# PCB_Schematic.net
KiCad netlist of a schematic drawn in Altium Designer
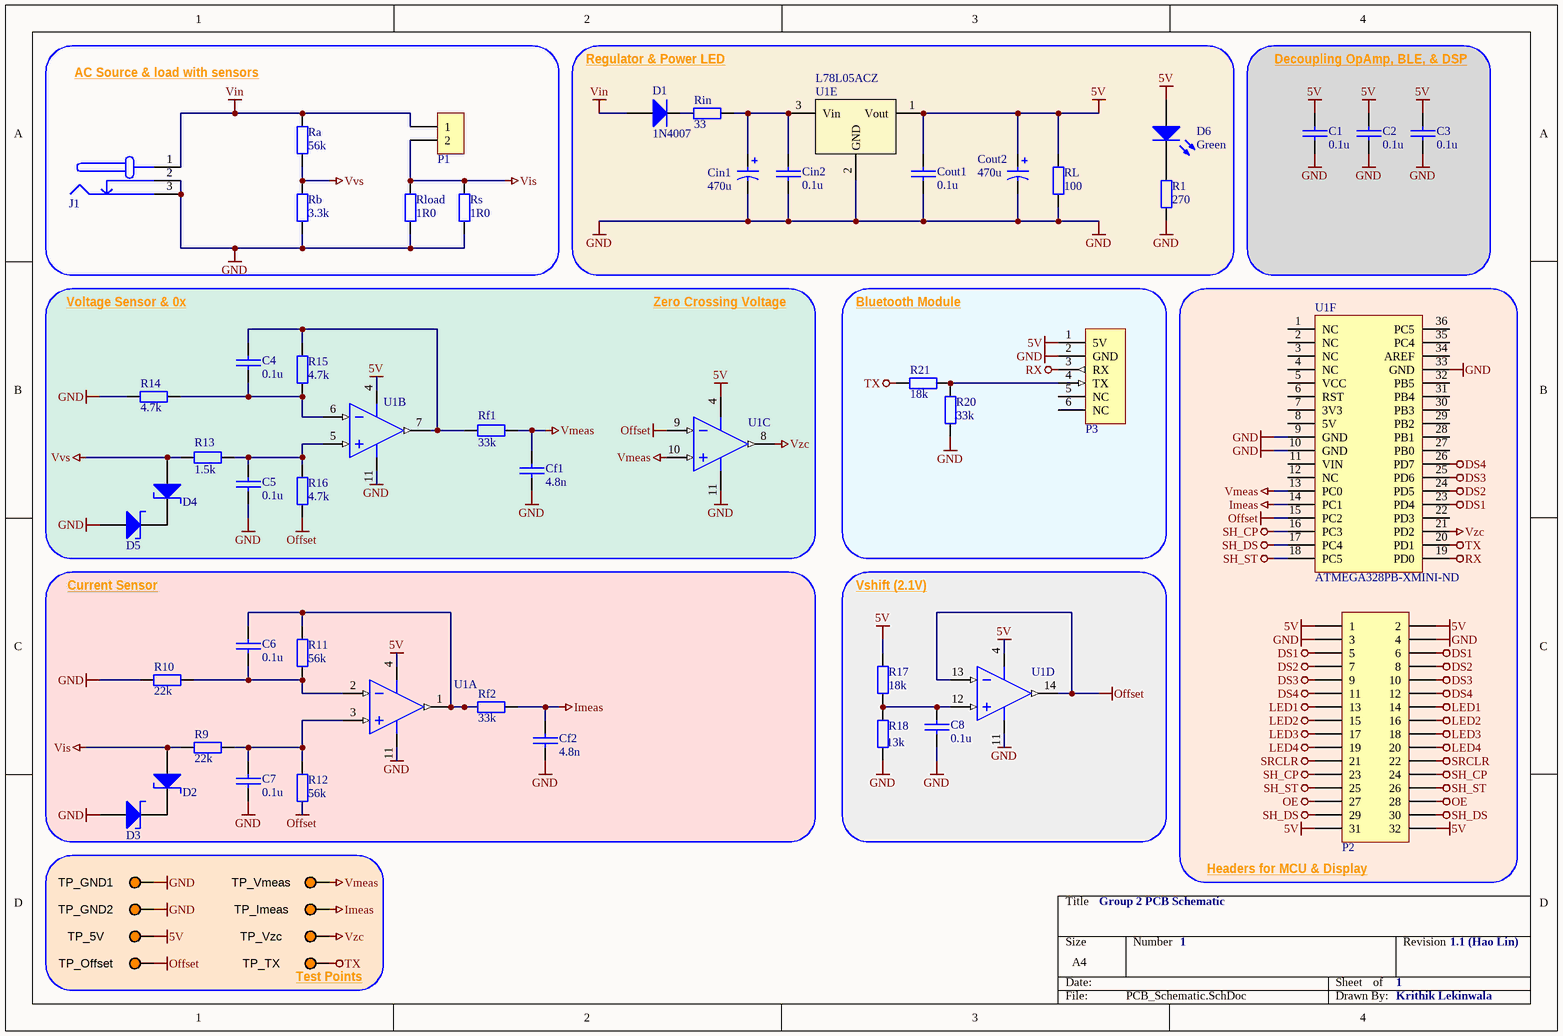
[diagram p0: PCB_Schematic.SchDoc]

(export (version "E")
  (design (tool "Eeschema 10.0.6"))
  (components
    (comp (ref "C1")
      (value "0.1u")
      (footprint "CCAP-5P0")
      (description "SMT ceramic capacitor 0805 size")
      (libsource (lib "EE209_Library") (part "CerCap_TH_5P0"))
    )
    (comp (ref "C2")
      (value "0.1u")
      (footprint "CCAP-5P0")
      (description "SMT ceramic capacitor 0805 size")
      (libsource (lib "EE209_Library") (part "CerCap_TH_5P0"))
    )
    (comp (ref "C3")
      (value "0.1u")
      (footprint "CCAP-5P0")
      (description "SMT ceramic capacitor 0805 size")
      (libsource (lib "EE209_Library") (part "CerCap_TH_5P0"))
    )
    (comp (ref "C4")
      (value "0.1u")
      (footprint "CCAP-5P0")
      (description "SMT ceramic capacitor 0805 size")
      (libsource (lib "EE209_Library") (part "CerCap_TH_5P0"))
    )
    (comp (ref "C5")
      (value "0.1u")
      (footprint "CCAP-5P0")
      (description "SMT ceramic capacitor 0805 size")
      (libsource (lib "EE209_Library") (part "CerCap_TH_5P0"))
    )
    (comp (ref "C6")
      (value "0.1u")
      (footprint "CCAP-5P0")
      (description "SMT ceramic capacitor 0805 size")
      (libsource (lib "EE209_Library") (part "CerCap_TH_5P0"))
    )
    (comp (ref "C7")
      (value "0.1u")
      (footprint "CCAP-5P0")
      (description "SMT ceramic capacitor 0805 size")
      (libsource (lib "EE209_Library") (part "CerCap_TH_5P0"))
    )
    (comp (ref "C8")
      (value "0.1u")
      (footprint "CCAP-5P0")
      (description "SMT ceramic capacitor 0805 size")
      (libsource (lib "EE209_Library") (part "CerCap_TH_5P0"))
    )
    (comp (ref "Cf1")
      (value "4.8n")
      (footprint "CCAP-5P0")
      (description "SMT ceramic capacitor 0805 size")
      (libsource (lib "EE209_Library") (part "CerCap_TH_5P0"))
    )
    (comp (ref "Cf2")
      (value "4.8n")
      (footprint "CCAP-5P0")
      (description "SMT ceramic capacitor 0805 size")
      (libsource (lib "EE209_Library") (part "CerCap_TH_5P0"))
    )
    (comp (ref "Cin1")
      (value "470u")
      (footprint "CAP-RAD-2.5mm Pitch")
      (description "Electrolytic capacitor with radial package, 2mm pitch and 5.2mm diameter")
      (fields (field (name "PUBLISHER") "Altium Limited"))
      (libsource (lib "EE209_Library") (part "ElecCap_TH_2P0"))
    )
    (comp (ref "Cin2")
      (value "0.1u")
      (footprint "CCAP-5P0")
      (description "SMT ceramic capacitor 0805 size")
      (libsource (lib "EE209_Library") (part "CerCap_TH_5P0"))
    )
    (comp (ref "Cout1")
      (value "0.1u")
      (footprint "CCAP-5P0")
      (description "SMT ceramic capacitor 0805 size")
      (libsource (lib "EE209_Library") (part "CerCap_TH_5P0"))
    )
    (comp (ref "Cout2")
      (value "470u")
      (footprint "CAP-RAD-2.5mm Pitch")
      (description "Electrolytic capacitor with radial package, 2mm pitch and 5.2mm diameter")
      (fields (field (name "PUBLISHER") "Altium Limited"))
      (libsource (lib "EE209_Library") (part "ElecCap_TH_2P0"))
    )
    (comp (ref "D1")
      (value "1N4007")
      (footprint "1N4007-MFG")
      (description "1N4007 1000V standard axial diode")
      (libsource (lib "EE209_Library") (part "1N4007_TH_4AX0"))
    )
    (comp (ref "D2")
      (value "BZX79-CXVX")
      (footprint "AXIAL-Zener-0.4")
      (description "Axial zener diode BZX79 series")
      (fields
        (field (name "MANUFACTURER") "Nexperia USA Inc.")
        (field (name "MANUFACTURER PART NUMBER") "BZX79-C4V7,143")
      )
      (libsource (lib "EE209_Library") (part "Zener_TH_4AX0"))
    )
    (comp (ref "D3")
      (value "BZX79-CXVX")
      (footprint "AXIAL-Zener-0.4")
      (description "Axial zener diode BZX79 series")
      (fields
        (field (name "MANUFACTURER") "Nexperia USA Inc.")
        (field (name "MANUFACTURER PART NUMBER") "BZX79-C4V7,143")
      )
      (libsource (lib "EE209_Library") (part "Zener_TH_4AX0"))
    )
    (comp (ref "D4")
      (value "BZX79-CXVX")
      (footprint "AXIAL-Zener-0.4")
      (description "Axial zener diode BZX79 series")
      (fields
        (field (name "MANUFACTURER") "Nexperia USA Inc.")
        (field (name "MANUFACTURER PART NUMBER") "BZX79-C4V7,143")
      )
      (libsource (lib "EE209_Library") (part "Zener_TH_4AX0"))
    )
    (comp (ref "D5")
      (value "BZX79-CXVX")
      (footprint "AXIAL-Zener-0.4")
      (description "Axial zener diode BZX79 series")
      (fields
        (field (name "MANUFACTURER") "Nexperia USA Inc.")
        (field (name "MANUFACTURER PART NUMBER") "BZX79-C4V7,143")
      )
      (libsource (lib "EE209_Library") (part "Zener_TH_4AX0"))
    )
    (comp (ref "D6")
      (value "Green")
      (footprint "LED")
      (description "Typical throughole GaAs LED with 2.54mm pitch")
      (fields (field (name "MANUFACTURER") "Generic Components") (field (name "PUBLISHER") "Altium Limited"))
      (libsource (lib "EE209_Library") (part "LED_TH_2P54"))
    )
    (comp (ref "J1")
      (value "DC barrel jack")
      (footprint "AC-Socket")
      (description "DC barrel jack connection to AC source")
      (libsource (lib "EE209_Library") (part "AC_Input"))
    )
    (comp (ref "P1")
      (value "Dual Banana Plugs")
      (footprint "Dual Banana Plug")
      (description "Dual banana plugs connection to the AC load")
      (fields (field (name "PUBLISHER") "Altium Limited"))
      (libsource (lib "EE209_Library") (part "AC_Output"))
    )
    (comp (ref "P2")
      (value "Display")
      (footprint "Display")
      (description "16-Pin Header Connecting Display")
      (libsource (lib "EE209_Library") (part "Display"))
    )
    (comp (ref "P3")
      (value "BLE Module Header")
      (footprint "HM10_HDR1X6")
      (description "2.54mm pitch 6-pin header for BLE module")
      (fields (field (name "PUBLISHER") "Altium Limited"))
      (libsource (lib "EE209_Library") (part "BLEModule_TH"))
    )
    (comp (ref "R1")
      (value "270")
      (footprint "AXIAL-0.4")
      (description "Through hole resistor")
      (fields (field (name "PUBLISHER") "Altium Limited"))
      (libsource (lib "EE209_Library") (part "Res_TH_0AX4"))
    )
    (comp (ref "R9")
      (value "22k")
      (footprint "AXIAL-0.4")
      (description "Through hole resistor")
      (fields (field (name "PUBLISHER") "Altium Limited"))
      (libsource (lib "") (part "Res_TH_0AX4_1"))
    )
    (comp (ref "R10")
      (value "22k")
      (footprint "AXIAL-0.4")
      (description "Through hole resistor")
      (fields (field (name "PUBLISHER") "Altium Limited"))
      (libsource (lib "") (part "Res_TH_0AX4_1"))
    )
    (comp (ref "R11")
      (value "56k")
      (footprint "AXIAL-0.4")
      (description "Through hole resistor")
      (fields (field (name "PUBLISHER") "Altium Limited"))
      (libsource (lib "EE209_Library") (part "Res_TH_0AX4"))
    )
    (comp (ref "R12")
      (value "56k")
      (footprint "AXIAL-0.4")
      (description "Through hole resistor")
      (fields (field (name "PUBLISHER") "Altium Limited"))
      (libsource (lib "EE209_Library") (part "Res_TH_0AX4"))
    )
    (comp (ref "R13")
      (value "1.5k")
      (footprint "AXIAL-0.4")
      (description "Through hole resistor")
      (fields (field (name "PUBLISHER") "Altium Limited"))
      (libsource (lib "") (part "Res_TH_0AX4_1"))
    )
    (comp (ref "R14")
      (value "4.7k")
      (footprint "AXIAL-0.4")
      (description "Through hole resistor")
      (fields (field (name "PUBLISHER") "Altium Limited"))
      (libsource (lib "") (part "Res_TH_0AX4_1"))
    )
    (comp (ref "R15")
      (value "4.7k")
      (footprint "AXIAL-0.4")
      (description "Through hole resistor")
      (fields (field (name "PUBLISHER") "Altium Limited"))
      (libsource (lib "EE209_Library") (part "Res_TH_0AX4"))
    )
    (comp (ref "R16")
      (value "4.7k")
      (footprint "AXIAL-0.4")
      (description "Through hole resistor")
      (fields (field (name "PUBLISHER") "Altium Limited"))
      (libsource (lib "EE209_Library") (part "Res_TH_0AX4"))
    )
    (comp (ref "R17")
      (value "18k")
      (footprint "AXIAL-0.4")
      (description "Through hole resistor")
      (fields (field (name "PUBLISHER") "Altium Limited"))
      (libsource (lib "EE209_Library") (part "Res_TH_0AX4"))
    )
    (comp (ref "R18")
      (value "13k")
      (footprint "AXIAL-0.4")
      (description "Through hole resistor")
      (fields (field (name "PUBLISHER") "Altium Limited"))
      (libsource (lib "EE209_Library") (part "Res_TH_0AX4"))
    )
    (comp (ref "R20")
      (value "33k")
      (footprint "AXIAL-0.4")
      (description "Through hole resistor")
      (fields (field (name "PUBLISHER") "Altium Limited"))
      (libsource (lib "EE209_Library") (part "Res_TH_0AX4"))
    )
    (comp (ref "R21")
      (value "18k")
      (footprint "AXIAL-0.4")
      (description "Through hole resistor")
      (fields (field (name "PUBLISHER") "Altium Limited"))
      (libsource (lib "") (part "Res_TH_0AX4_3"))
    )
    (comp (ref "Ra")
      (value "56k")
      (footprint "AXIAL-0.4")
      (description "Through hole resistor")
      (fields (field (name "PUBLISHER") "Altium Limited"))
      (libsource (lib "EE209_Library") (part "Res_TH_0AX4"))
    )
    (comp (ref "Rb")
      (value "3.3k")
      (footprint "AXIAL-0.4")
      (description "Through hole resistor")
      (fields (field (name "PUBLISHER") "Altium Limited"))
      (libsource (lib "EE209_Library") (part "Res_TH_0AX4"))
    )
    (comp (ref "Rf1")
      (value "33k")
      (footprint "AXIAL-0.4")
      (description "Through hole resistor")
      (fields (field (name "PUBLISHER") "Altium Limited"))
      (libsource (lib "") (part "Res_TH_0AX4_1"))
    )
    (comp (ref "Rf2")
      (value "33k")
      (footprint "AXIAL-0.4")
      (description "Through hole resistor")
      (fields (field (name "PUBLISHER") "Altium Limited"))
      (libsource (lib "") (part "Res_TH_0AX4_1"))
    )
    (comp (ref "Rin")
      (value "33")
      (footprint "AXIAL-0.4")
      (description "Through hole resistor")
      (fields (field (name "PUBLISHER") "Altium Limited"))
      (libsource (lib "") (part "Res_TH_0AX4_1"))
    )
    (comp (ref "RL")
      (value "100")
      (footprint "AXIAL-0.4")
      (description "Through hole resistor")
      (fields (field (name "PUBLISHER") "Altium Limited"))
      (libsource (lib "EE209_Library") (part "Res_TH_0AX4"))
    )
    (comp (ref "Rload")
      (value "1R0")
      (footprint "AXIAL-0.4")
      (description "Through hole resistor")
      (fields (field (name "PUBLISHER") "Altium Limited"))
      (libsource (lib "EE209_Library") (part "Res_TH_0AX4"))
    )
    (comp (ref "Rs")
      (value "1R0")
      (footprint "AXIAL-0.4")
      (description "Through hole resistor")
      (fields (field (name "PUBLISHER") "Altium Limited"))
      (libsource (lib "") (part "Res_TH_0AX4_2"))
    )
    (comp (ref "TP_5V")
      (value "5003")
      (footprint "TP_TH")
      (description "Test Point, Orange, 1-Pin THD, RoHS")
      (libsource (lib "EE209_Library") (part "TestPoint"))
    )
    (comp (ref "TP_GND1")
      (value "5003")
      (footprint "TP_TH")
      (description "Test Point, Orange, 1-Pin THD, RoHS")
      (libsource (lib "EE209_Library") (part "TestPoint"))
    )
    (comp (ref "TP_GND2")
      (value "5003")
      (footprint "TP_TH")
      (description "Test Point, Orange, 1-Pin THD, RoHS")
      (libsource (lib "EE209_Library") (part "TestPoint"))
    )
    (comp (ref "TP_Imeas")
      (value "5003")
      (footprint "TP_TH")
      (description "Test Point, Orange, 1-Pin THD, RoHS")
      (libsource (lib "EE209_Library") (part "TestPoint"))
    )
    (comp (ref "TP_Offset")
      (value "5003")
      (footprint "TP_TH")
      (description "Test Point, Orange, 1-Pin THD, RoHS")
      (libsource (lib "EE209_Library") (part "TestPoint"))
    )
    (comp (ref "TP_TX")
      (value "5003")
      (footprint "TP_TH")
      (description "Test Point, Orange, 1-Pin THD, RoHS")
      (libsource (lib "EE209_Library") (part "TestPoint"))
    )
    (comp (ref "TP_Vmeas")
      (value "5003")
      (footprint "TP_TH")
      (description "Test Point, Orange, 1-Pin THD, RoHS")
      (libsource (lib "EE209_Library") (part "TestPoint"))
    )
    (comp (ref "TP_Vzc")
      (value "5003")
      (footprint "TP_TH")
      (description "Test Point, Orange, 1-Pin THD, RoHS")
      (libsource (lib "EE209_Library") (part "TestPoint"))
    )
    (comp (ref "U1")
      (value "LM324")
      (footprint "DIP-14")
      (description "IC OPAMP GP 14DIP")
      (fields
        (field (name "MANUFACTURER") "ON Semiconductor")
        (field (name "MANUFACTURER PART NUMBER") "LM324N")
      )
      (libsource (lib "EE209_Library") (part "LM324N_TH_DIP16"))
    )
    (comp (ref "U1E")
      (value "L78L05ACZ")
      (footprint "TO-92")
      (description "Voltage Regulator 5V")
      (fields
        (field (name "MANUFACTURER") "ON Semiconductor")
        (field (name "MANUFACTURER PART NUMBER") "LM78L05ACZX")
      )
      (libsource (lib "EE209_Library") (part "L78L05_TH_TO92"))
    )
    (comp (ref "U1F")
      (value "ATmega328PB Xplained Mini Header")
      (footprint "ATmeg328P Xplained")
      (description "Dual 18-pin headers connecting to ATmega328PB Xplained Mini")
      (fields
        (field (name "MANUFACTURER") "Microchip Technology")
        (field (name "MANUFACTURER PART NUMBER") "ATMEGA328PB-XMINI")
        (field (name "SUPPLIER PART NUMBER 1") "ATMEGA328PB-XMINI-ND")
      )
      (libsource (lib "EE209_Library") (part "ATmega328PBXplained_TH"))
    )
  )
  (nets
    (net (code "1") (name "5V") (class "Default")
      (node (ref "C1") (pin "1") (pinfunction "1_1") (pintype "passive"))
      (node (ref "C2") (pin "1") (pinfunction "1_1") (pintype "passive"))
      (node (ref "C3") (pin "1") (pinfunction "1_1") (pintype "passive"))
      (node (ref "Cout1") (pin "1") (pinfunction "1_1") (pintype "passive"))
      (node (ref "Cout2") (pin "1") (pinfunction "1_1") (pintype "passive"))
      (node (ref "D6") (pin "1") (pinfunction "A_1") (pintype "passive"))
      (node (ref "P2") (pin "1") (pinfunction "1_1") (pintype "passive"))
      (node (ref "P2") (pin "2") (pinfunction "2_2") (pintype "passive"))
      (node (ref "P2") (pin "31") (pinfunction "31_31") (pintype "passive"))
      (node (ref "P2") (pin "32") (pinfunction "32_32") (pintype "passive"))
      (node (ref "P3") (pin "1") (pinfunction "5V_1") (pintype "passive"))
      (node (ref "R17") (pin "2") (pinfunction "2_2") (pintype "passive"))
      (node (ref "RL") (pin "2") (pinfunction "2_2") (pintype "passive"))
      (node (ref "TP_5V") (pin "1") (pinfunction "1_1") (pintype "passive"))
      (node (ref "U1") (pin "4") (pinfunction "VDD_4") (pintype "power_in"))
      (node (ref "U1E") (pin "1") (pinfunction "Vout_1") (pintype "passive"))
    )
    (net (code "2") (name "DS1") (class "Default")
      (node (ref "P2") (pin "5") (pinfunction "5_5") (pintype "passive"))
      (node (ref "P2") (pin "6") (pinfunction "6_6") (pintype "passive"))
      (node (ref "U1F") (pin "23") (pinfunction "PD4_23") (pintype "passive"))
    )
    (net (code "3") (name "DS2") (class "Default")
      (node (ref "P2") (pin "7") (pinfunction "7_7") (pintype "passive"))
      (node (ref "P2") (pin "8") (pinfunction "8_8") (pintype "passive"))
      (node (ref "U1F") (pin "24") (pinfunction "PD5_24") (pintype "passive"))
    )
    (net (code "4") (name "DS3") (class "Default")
      (node (ref "P2") (pin "10") (pinfunction "10_10") (pintype "passive"))
      (node (ref "P2") (pin "9") (pinfunction "9_9") (pintype "passive"))
      (node (ref "U1F") (pin "25") (pinfunction "PD6_25") (pintype "passive"))
    )
    (net (code "5") (name "DS4") (class "Default")
      (node (ref "P2") (pin "11") (pinfunction "11_11") (pintype "passive"))
      (node (ref "P2") (pin "12") (pinfunction "12_12") (pintype "passive"))
      (node (ref "U1F") (pin "26") (pinfunction "PD7_26") (pintype "passive"))
    )
    (net (code "6") (name "GND") (class "Default")
      (node (ref "C1") (pin "2") (pinfunction "2_2") (pintype "passive"))
      (node (ref "C2") (pin "2") (pinfunction "2_2") (pintype "passive"))
      (node (ref "C3") (pin "2") (pinfunction "2_2") (pintype "passive"))
      (node (ref "C5") (pin "2") (pinfunction "2_2") (pintype "passive"))
      (node (ref "C7") (pin "2") (pinfunction "2_2") (pintype "passive"))
      (node (ref "C8") (pin "2") (pinfunction "2_2") (pintype "passive"))
      (node (ref "Cf1") (pin "2") (pinfunction "2_2") (pintype "passive"))
      (node (ref "Cf2") (pin "2") (pinfunction "2_2") (pintype "passive"))
      (node (ref "Cin1") (pin "2") (pinfunction "2_2") (pintype "passive"))
      (node (ref "Cin2") (pin "2") (pinfunction "2_2") (pintype "passive"))
      (node (ref "Cout1") (pin "2") (pinfunction "2_2") (pintype "passive"))
      (node (ref "Cout2") (pin "2") (pinfunction "2_2") (pintype "passive"))
      (node (ref "D3") (pin "1") (pinfunction "A_1") (pintype "passive"))
      (node (ref "D5") (pin "1") (pinfunction "A_1") (pintype "passive"))
      (node (ref "J1") (pin "2") (pinfunction "GND_ALT_2") (pintype "power_in"))
      (node (ref "J1") (pin "3") (pinfunction "GND_3") (pintype "power_in"))
      (node (ref "P2") (pin "3") (pinfunction "3_3") (pintype "passive"))
      (node (ref "P2") (pin "4") (pinfunction "4_4") (pintype "passive"))
      (node (ref "P3") (pin "2") (pinfunction "GND_2") (pintype "passive"))
      (node (ref "R1") (pin "1") (pinfunction "1_1") (pintype "passive"))
      (node (ref "R10") (pin "1") (pinfunction "1_1") (pintype "passive"))
      (node (ref "R14") (pin "1") (pinfunction "1_1") (pintype "passive"))
      (node (ref "R18") (pin "1") (pinfunction "1_1") (pintype "passive"))
      (node (ref "R20") (pin "1") (pinfunction "1_1") (pintype "passive"))
      (node (ref "RL") (pin "1") (pinfunction "1_1") (pintype "passive"))
      (node (ref "Rb") (pin "1") (pinfunction "1_1") (pintype "passive"))
      (node (ref "Rload") (pin "1") (pinfunction "1_1") (pintype "passive"))
      (node (ref "Rs") (pin "2") (pinfunction "2_2") (pintype "passive"))
      (node (ref "TP_GND1") (pin "1") (pinfunction "1_1") (pintype "passive"))
      (node (ref "TP_GND2") (pin "1") (pinfunction "1_1") (pintype "passive"))
      (node (ref "U1") (pin "11") (pinfunction "VSS_11") (pintype "power_in"))
      (node (ref "U1E") (pin "2") (pinfunction "GND_2") (pintype "passive"))
      (node (ref "U1F") (pin "10") (pinfunction "GND_10") (pintype "power_in"))
      (node (ref "U1F") (pin "33") (pinfunction "GND_33") (pintype "passive"))
      (node (ref "U1F") (pin "9") (pinfunction "GND_9") (pintype "power_in"))
    )
    (net (code "7") (name "Imeas") (class "Default")
      (node (ref "Cf2") (pin "1") (pinfunction "1_1") (pintype "passive"))
      (node (ref "Rf2") (pin "2") (pinfunction "2_2") (pintype "passive"))
      (node (ref "TP_Imeas") (pin "1") (pinfunction "1_1") (pintype "passive"))
      (node (ref "U1F") (pin "14") (pinfunction "PC1_14") (pintype "passive"))
    )
    (net (code "8") (name "LED1") (class "Default")
      (node (ref "P2") (pin "13") (pinfunction "13_13") (pintype "passive"))
      (node (ref "P2") (pin "14") (pinfunction "14_14") (pintype "passive"))
    )
    (net (code "9") (name "LED2") (class "Default")
      (node (ref "P2") (pin "15") (pinfunction "15_15") (pintype "passive"))
      (node (ref "P2") (pin "16") (pinfunction "16_16") (pintype "passive"))
    )
    (net (code "10") (name "LED3") (class "Default")
      (node (ref "P2") (pin "17") (pinfunction "17_17") (pintype "passive"))
      (node (ref "P2") (pin "18") (pinfunction "18_18") (pintype "passive"))
    )
    (net (code "11") (name "LED4") (class "Default")
      (node (ref "P2") (pin "19") (pinfunction "19_19") (pintype "passive"))
      (node (ref "P2") (pin "20") (pinfunction "20_20") (pintype "passive"))
    )
    (net (code "12") (name "Net-(D1-K)") (class "Default")
      (node (ref "D1") (pin "2") (pinfunction "K_2") (pintype "passive"))
      (node (ref "Rin") (pin "1") (pinfunction "1_1") (pintype "passive"))
    )
    (net (code "13") (name "Net-(D2-K)") (class "Default")
      (node (ref "D2") (pin "2") (pinfunction "K_2") (pintype "passive"))
      (node (ref "D3") (pin "2") (pinfunction "K_2") (pintype "passive"))
    )
    (net (code "14") (name "Net-(D4-K)") (class "Default")
      (node (ref "D4") (pin "2") (pinfunction "K_2") (pintype "passive"))
      (node (ref "D5") (pin "2") (pinfunction "K_2") (pintype "passive"))
    )
    (net (code "15") (name "Net-(D6-K)") (class "Default")
      (node (ref "D6") (pin "2") (pinfunction "K_2") (pintype "passive"))
      (node (ref "R1") (pin "2") (pinfunction "2_2") (pintype "passive"))
    )
    (net (code "16") (name "Net-(P3-TX)") (class "Default")
      (node (ref "P3") (pin "4") (pinfunction "TX_4") (pintype "input"))
      (node (ref "R20") (pin "2") (pinfunction "2_2") (pintype "passive"))
      (node (ref "R21") (pin "1") (pinfunction "1_1") (pintype "passive"))
    )
    (net (code "17") (name "Net-(U1A-VINA+)") (class "Default")
      (node (ref "C7") (pin "1") (pinfunction "1_1") (pintype "passive"))
      (node (ref "R12") (pin "2") (pinfunction "2_2") (pintype "passive"))
      (node (ref "R9") (pin "2") (pinfunction "2_2") (pintype "passive"))
      (node (ref "U1") (pin "3") (pinfunction "VINA+_3") (pintype "input"))
    )
    (net (code "18") (name "Net-(U1A-VINA-)") (class "Default")
      (node (ref "C6") (pin "2") (pinfunction "2_2") (pintype "passive"))
      (node (ref "R10") (pin "2") (pinfunction "2_2") (pintype "passive"))
      (node (ref "R11") (pin "1") (pinfunction "1_1") (pintype "passive"))
      (node (ref "U1") (pin "2") (pinfunction "VINA-_2") (pintype "input"))
    )
    (net (code "19") (name "Net-(U1A-VOUTA)") (class "Default")
      (node (ref "C6") (pin "1") (pinfunction "1_1") (pintype "passive"))
      (node (ref "R11") (pin "2") (pinfunction "2_2") (pintype "passive"))
      (node (ref "Rf2") (pin "1") (pinfunction "1_1") (pintype "passive"))
      (node (ref "U1") (pin "1") (pinfunction "VOUTA_1") (pintype "output"))
    )
    (net (code "20") (name "Net-(U1B-VINB+)") (class "Default")
      (node (ref "C5") (pin "1") (pinfunction "1_1") (pintype "passive"))
      (node (ref "R13") (pin "2") (pinfunction "2_2") (pintype "passive"))
      (node (ref "R16") (pin "2") (pinfunction "2_2") (pintype "passive"))
      (node (ref "U1") (pin "5") (pinfunction "VINB+_5") (pintype "input"))
    )
    (net (code "21") (name "Net-(U1B-VINB-)") (class "Default")
      (node (ref "C4") (pin "2") (pinfunction "2_2") (pintype "passive"))
      (node (ref "R14") (pin "2") (pinfunction "2_2") (pintype "passive"))
      (node (ref "R15") (pin "1") (pinfunction "1_1") (pintype "passive"))
      (node (ref "U1") (pin "6") (pinfunction "VINB-_6") (pintype "input"))
    )
    (net (code "22") (name "Net-(U1B-VOUTB)") (class "Default")
      (node (ref "C4") (pin "1") (pinfunction "1_1") (pintype "passive"))
      (node (ref "R15") (pin "2") (pinfunction "2_2") (pintype "passive"))
      (node (ref "Rf1") (pin "1") (pinfunction "1_1") (pintype "passive"))
      (node (ref "U1") (pin "7") (pinfunction "VOUTB_7") (pintype "output"))
    )
    (net (code "23") (name "Net-(U1D-VIND+)") (class "Default")
      (node (ref "C8") (pin "1") (pinfunction "1_1") (pintype "passive"))
      (node (ref "R17") (pin "1") (pinfunction "1_1") (pintype "passive"))
      (node (ref "R18") (pin "2") (pinfunction "2_2") (pintype "passive"))
      (node (ref "U1") (pin "12") (pinfunction "VIND+_12") (pintype "input"))
    )
    (net (code "24") (name "Net-(U1E-Vin)") (class "Default")
      (node (ref "Cin1") (pin "1") (pinfunction "1_1") (pintype "passive"))
      (node (ref "Cin2") (pin "1") (pinfunction "1_1") (pintype "passive"))
      (node (ref "Rin") (pin "2") (pinfunction "2_2") (pintype "passive"))
      (node (ref "U1E") (pin "3") (pinfunction "Vin_3") (pintype "passive"))
    )
    (net (code "25") (name "OE") (class "Default")
      (node (ref "P2") (pin "27") (pinfunction "27_27") (pintype "passive"))
      (node (ref "P2") (pin "28") (pinfunction "28_28") (pintype "passive"))
    )
    (net (code "26") (name "Offset") (class "Default")
      (node (ref "R12") (pin "1") (pinfunction "1_1") (pintype "passive"))
      (node (ref "R16") (pin "1") (pinfunction "1_1") (pintype "passive"))
      (node (ref "TP_Offset") (pin "1") (pinfunction "1_1") (pintype "passive"))
      (node (ref "U1") (pin "13") (pinfunction "VIND-_13") (pintype "input"))
      (node (ref "U1") (pin "14") (pinfunction "VOUTD_14") (pintype "output"))
      (node (ref "U1") (pin "9") (pinfunction "VINC-_9") (pintype "input"))
      (node (ref "U1F") (pin "15") (pinfunction "PC2_15") (pintype "passive"))
    )
    (net (code "27") (name "RX") (class "Default")
      (node (ref "P3") (pin "3") (pinfunction "RX_3") (pintype "output"))
      (node (ref "U1F") (pin "19") (pinfunction "PD0_19") (pintype "passive"))
    )
    (net (code "28") (name "SH_CP") (class "Default")
      (node (ref "P2") (pin "23") (pinfunction "23_23") (pintype "passive"))
      (node (ref "P2") (pin "24") (pinfunction "24_24") (pintype "passive"))
      (node (ref "U1F") (pin "16") (pinfunction "PC3_16") (pintype "passive"))
    )
    (net (code "29") (name "SH_DS") (class "Default")
      (node (ref "P2") (pin "29") (pinfunction "29_29") (pintype "passive"))
      (node (ref "P2") (pin "30") (pinfunction "30_30") (pintype "passive"))
      (node (ref "U1F") (pin "17") (pinfunction "PC4_17") (pintype "passive"))
    )
    (net (code "30") (name "SH_ST") (class "Default")
      (node (ref "P2") (pin "25") (pinfunction "25_25") (pintype "passive"))
      (node (ref "P2") (pin "26") (pinfunction "26_26") (pintype "passive"))
      (node (ref "U1F") (pin "18") (pinfunction "PC5_18") (pintype "passive"))
    )
    (net (code "31") (name "SRCLR") (class "Default")
      (node (ref "P2") (pin "21") (pinfunction "21_21") (pintype "passive"))
      (node (ref "P2") (pin "22") (pinfunction "22_22") (pintype "passive"))
    )
    (net (code "32") (name "TX") (class "Default")
      (node (ref "R21") (pin "2") (pinfunction "2_2") (pintype "passive"))
      (node (ref "TP_TX") (pin "1") (pinfunction "1_1") (pintype "passive"))
      (node (ref "U1F") (pin "20") (pinfunction "PD1_20") (pintype "passive"))
    )
    (net (code "33") (name "Vin") (class "Default")
      (node (ref "D1") (pin "1") (pinfunction "A_1") (pintype "passive"))
      (node (ref "J1") (pin "1") (pinfunction "VCC_1") (pintype "power_in"))
      (node (ref "P1") (pin "1") (pinfunction "1_1") (pintype "passive"))
      (node (ref "Ra") (pin "2") (pinfunction "2_2") (pintype "passive"))
    )
    (net (code "34") (name "Vis") (class "Default")
      (node (ref "D2") (pin "1") (pinfunction "A_1") (pintype "passive"))
      (node (ref "P1") (pin "2") (pinfunction "2_2") (pintype "passive"))
      (node (ref "R9") (pin "1") (pinfunction "1_1") (pintype "passive"))
      (node (ref "Rload") (pin "2") (pinfunction "2_2") (pintype "passive"))
      (node (ref "Rs") (pin "1") (pinfunction "1_1") (pintype "passive"))
    )
    (net (code "35") (name "Vmeas") (class "Default")
      (node (ref "Cf1") (pin "1") (pinfunction "1_1") (pintype "passive"))
      (node (ref "Rf1") (pin "2") (pinfunction "2_2") (pintype "passive"))
      (node (ref "TP_Vmeas") (pin "1") (pinfunction "1_1") (pintype "passive"))
      (node (ref "U1") (pin "10") (pinfunction "VINC+_10") (pintype "input"))
      (node (ref "U1F") (pin "13") (pinfunction "PC0_13") (pintype "passive"))
    )
    (net (code "36") (name "Vvs") (class "Default")
      (node (ref "D4") (pin "1") (pinfunction "A_1") (pintype "passive"))
      (node (ref "R13") (pin "1") (pinfunction "1_1") (pintype "passive"))
      (node (ref "Ra") (pin "1") (pinfunction "1_1") (pintype "passive"))
      (node (ref "Rb") (pin "2") (pinfunction "2_2") (pintype "passive"))
    )
    (net (code "37") (name "Vzc") (class "Default")
      (node (ref "TP_Vzc") (pin "1") (pinfunction "1_1") (pintype "passive"))
      (node (ref "U1") (pin "8") (pinfunction "VOUTC_8") (pintype "output"))
      (node (ref "U1F") (pin "21") (pinfunction "PD2_21") (pintype "passive"))
    )
    (net (code "38") (name "unconnected-(P3-NC-Pad5)") (class "Default")
      (node (ref "P3") (pin "5") (pinfunction "NC_5") (pintype "passive"))
    )
    (net (code "39") (name "unconnected-(P3-NC-Pad6)") (class "Default")
      (node (ref "P3") (pin "6") (pinfunction "NC_6") (pintype "passive"))
    )
    (net (code "40") (name "unconnected-(U1C-VDD-Pad4)") (class "Default")
      (node (ref "U1") (pin "4") (pinfunction "VDD_4") (pintype "power_in"))
    )
    (net (code "41") (name "unconnected-(U1C-VSS-Pad11)") (class "Default")
      (node (ref "U1") (pin "11") (pinfunction "VSS_11") (pintype "power_in"))
    )
    (net (code "42") (name "unconnected-(U1F-3V3-Pad7)") (class "Default")
      (node (ref "U1F") (pin "7") (pinfunction "3V3_7") (pintype "passive"))
    )
    (net (code "43") (name "unconnected-(U1F-5V-Pad8)") (class "Default")
      (node (ref "U1F") (pin "8") (pinfunction "5V_8") (pintype "power_in"))
    )
    (net (code "44") (name "unconnected-(U1F-AREF-Pad34)") (class "Default")
      (node (ref "U1F") (pin "34") (pinfunction "AREF_34") (pintype "passive"))
    )
    (net (code "45") (name "unconnected-(U1F-NC-Pad1)") (class "Default")
      (node (ref "U1F") (pin "1") (pinfunction "NC_1") (pintype "passive"))
    )
    (net (code "46") (name "unconnected-(U1F-NC-Pad2)") (class "Default")
      (node (ref "U1F") (pin "2") (pinfunction "NC_2") (pintype "passive"))
    )
    (net (code "47") (name "unconnected-(U1F-NC-Pad3)") (class "Default")
      (node (ref "U1F") (pin "3") (pinfunction "NC_3") (pintype "passive"))
    )
    (net (code "48") (name "unconnected-(U1F-NC-Pad4)") (class "Default")
      (node (ref "U1F") (pin "4") (pinfunction "NC_4") (pintype "passive"))
    )
    (net (code "49") (name "unconnected-(U1F-NC-Pad12)") (class "Default")
      (node (ref "U1F") (pin "12") (pinfunction "NC_12") (pintype "passive"))
    )
    (net (code "50") (name "unconnected-(U1F-PB0-Pad27)") (class "Default")
      (node (ref "U1F") (pin "27") (pinfunction "PB0_27") (pintype "passive"))
    )
    (net (code "51") (name "unconnected-(U1F-PB1-Pad28)") (class "Default")
      (node (ref "U1F") (pin "28") (pinfunction "PB1_28") (pintype "passive"))
    )
    (net (code "52") (name "unconnected-(U1F-PB2-Pad29)") (class "Default")
      (node (ref "U1F") (pin "29") (pinfunction "PB2_29") (pintype "passive"))
    )
    (net (code "53") (name "unconnected-(U1F-PB3-Pad30)") (class "Default")
      (node (ref "U1F") (pin "30") (pinfunction "PB3_30") (pintype "passive"))
    )
    (net (code "54") (name "unconnected-(U1F-PB4-Pad31)") (class "Default")
      (node (ref "U1F") (pin "31") (pinfunction "PB4_31") (pintype "passive"))
    )
    (net (code "55") (name "unconnected-(U1F-PB5-Pad32)") (class "Default")
      (node (ref "U1F") (pin "32") (pinfunction "PB5_32") (pintype "passive"))
    )
    (net (code "56") (name "unconnected-(U1F-PC4-Pad35)") (class "Default")
      (node (ref "U1F") (pin "35") (pinfunction "PC4_35") (pintype "passive"))
    )
    (net (code "57") (name "unconnected-(U1F-PC5-Pad36)") (class "Default")
      (node (ref "U1F") (pin "36") (pinfunction "PC5_36") (pintype "passive"))
    )
    (net (code "58") (name "unconnected-(U1F-PD3-Pad22)") (class "Default")
      (node (ref "U1F") (pin "22") (pinfunction "PD3_22") (pintype "passive"))
    )
    (net (code "59") (name "unconnected-(U1F-RST-Pad6)") (class "Default")
      (node (ref "U1F") (pin "6") (pinfunction "RST_6") (pintype "passive"))
    )
    (net (code "60") (name "unconnected-(U1F-VCC-Pad5)") (class "Default")
      (node (ref "U1F") (pin "5") (pinfunction "VCC_5") (pintype "power_in"))
    )
    (net (code "61") (name "unconnected-(U1F-VIN-Pad11)") (class "Default")
      (node (ref "U1F") (pin "11") (pinfunction "VIN_11") (pintype "power_in"))
    )
  )
)
